# 06_-_CONNECTORS_1.net
KiCad netlist of a schematic drawn in Altium Designer
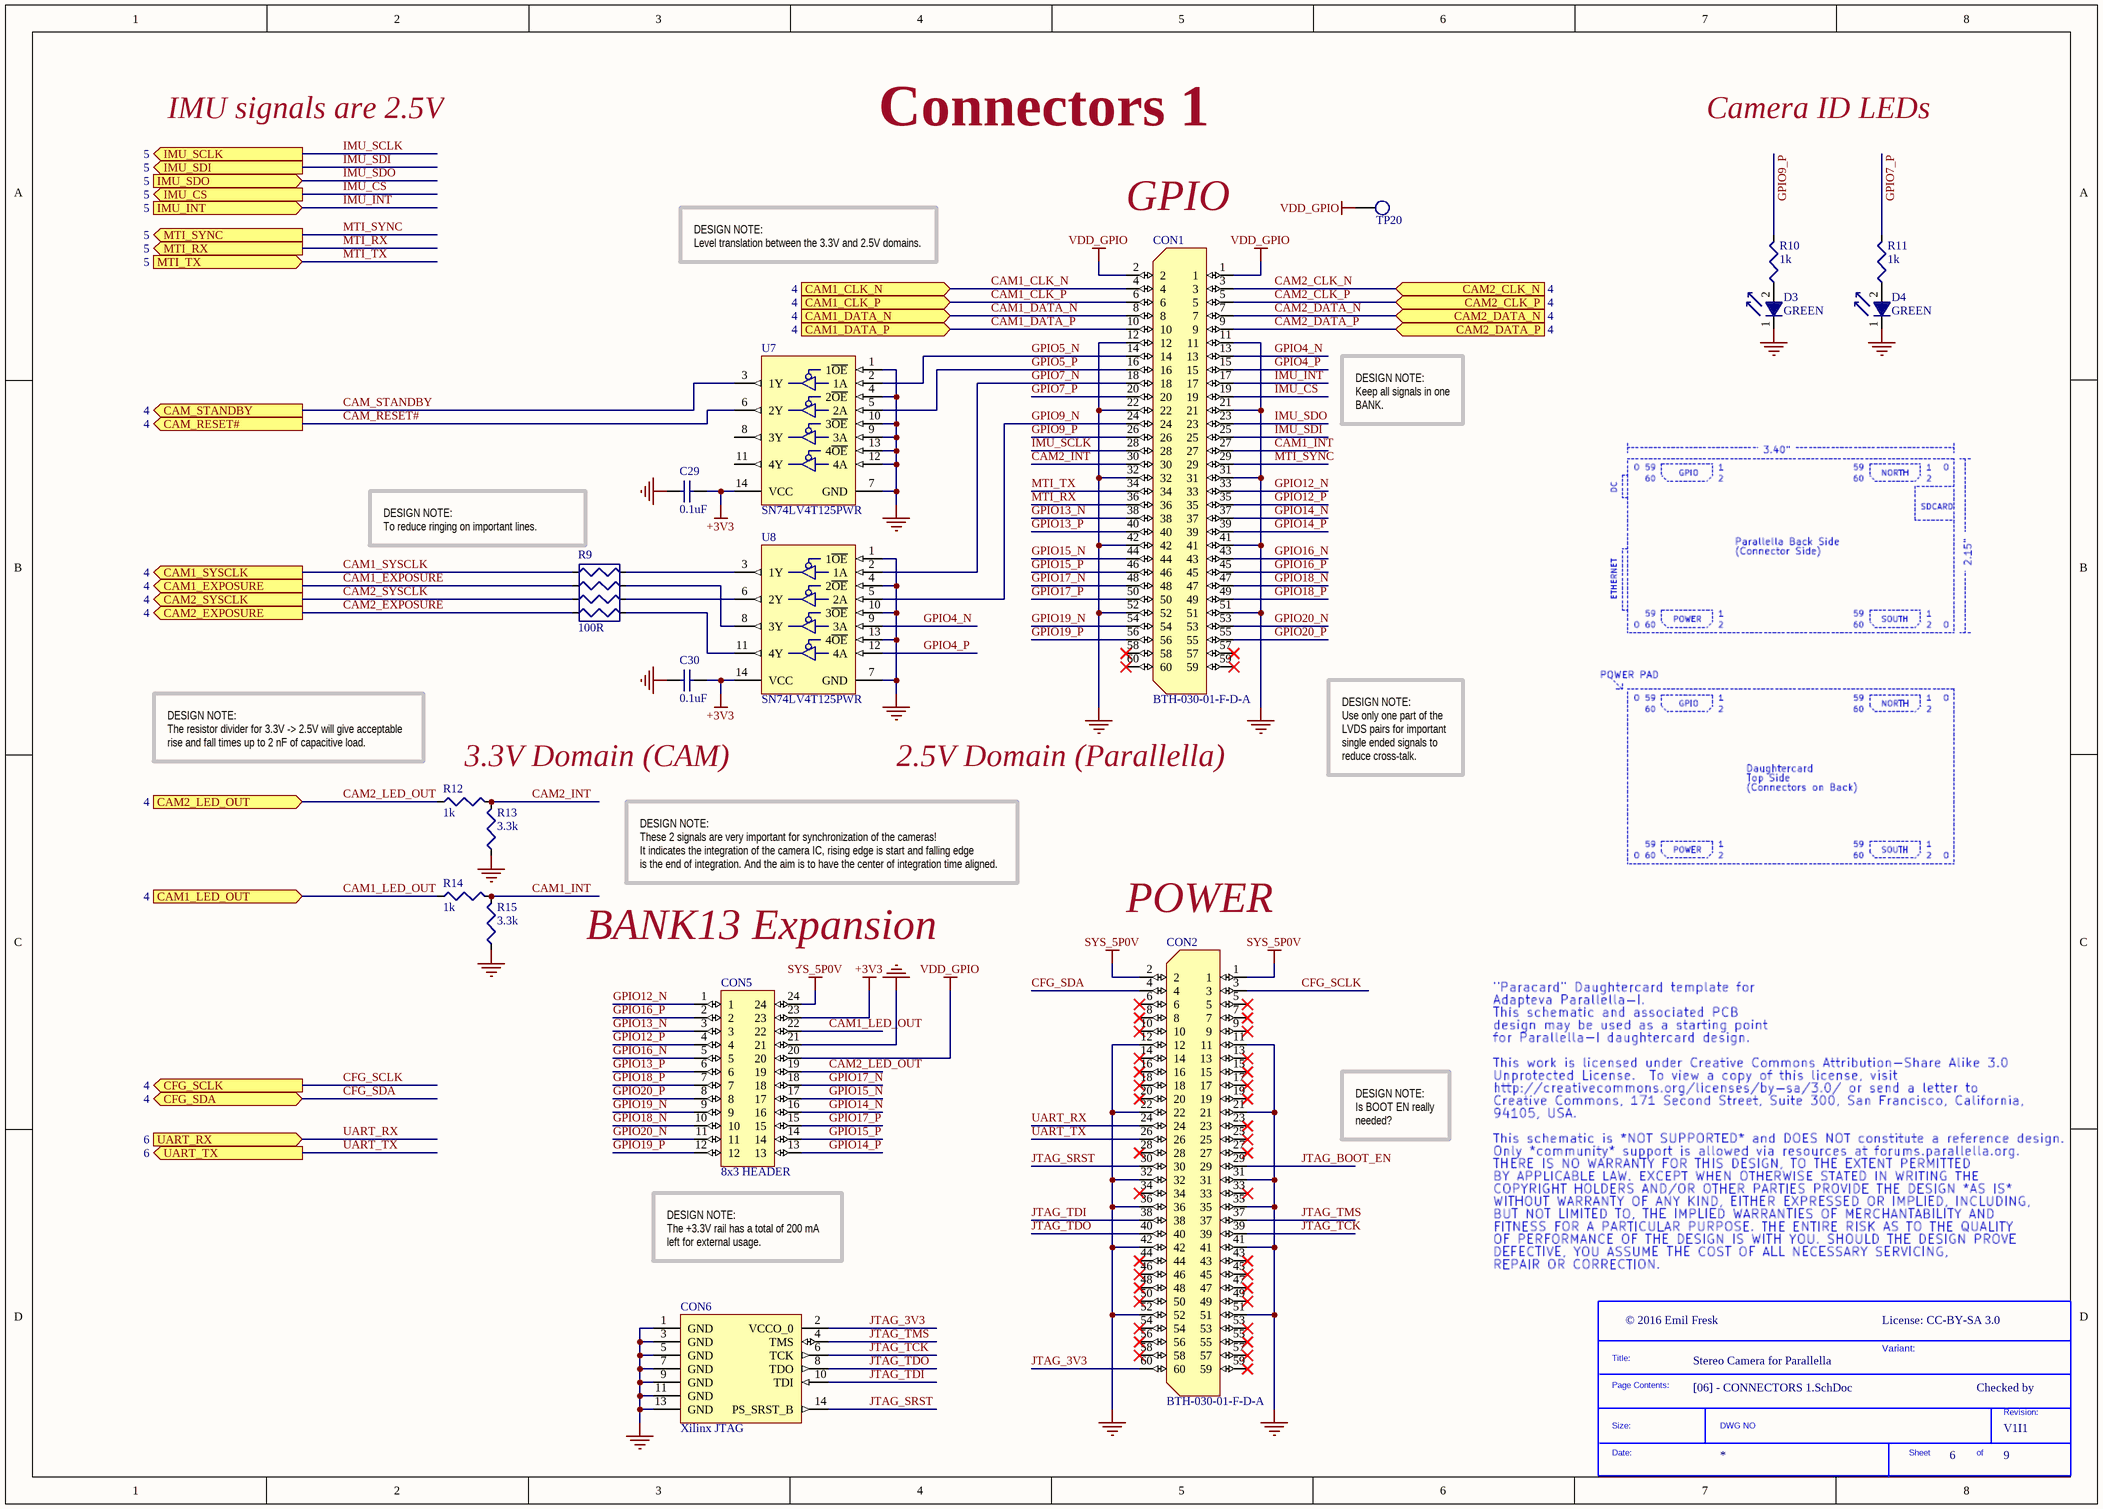
[diagram p0: [06] - CONNECTORS 1.SchDoc]

(export (version "E")
  (design (tool "Eeschema 10.0.6"))
  (components
    (comp (ref "C29")
      (value "0.1uF")
      (footprint "C0603L")
      (description "CAP CER 0.1UF 50V 10% X7R 0603")
      (fields
        (field (name "MANUFACTURER") "Murata Electronics North America")
        (field (name "MANUFACTURER PART NUMBER") "GRM188R71H104KA93J")
      )
      (libsource (lib "Capacitors") (part "GRM188R71H104KA93J"))
    )
    (comp (ref "C30")
      (value "0.1uF")
      (footprint "C0603L")
      (description "CAP CER 0.1UF 50V 10% X7R 0603")
      (fields
        (field (name "MANUFACTURER") "Murata Electronics North America")
        (field (name "MANUFACTURER PART NUMBER") "GRM188R71H104KA93J")
      )
      (libsource (lib "Capacitors") (part "GRM188R71H104KA93J"))
    )
    (comp (ref "CON1")
      (value "BTH-030-01-F-D-A")
      (footprint "BTH-030-01-X-D-A-K")
      (description "CONN RCPT 60POS 0.5MM SMD")
      (fields (field (name "MANUFACTURER") "Samtec Inc"))
      (libsource (lib "Connectors") (part "BTH-030-01-F-D-A"))
    )
    (comp (ref "CON2")
      (value "BTH-030-01-F-D-A")
      (footprint "BTH-030-01-X-D-A-K")
      (description "CONN RCPT 60POS 0.5MM SMD")
      (fields (field (name "MANUFACTURER") "Samtec Inc"))
      (libsource (lib "Connectors") (part "BTH-030-01-F-D-A"))
    )
    (comp (ref "CON5")
      (value "8x3 HEADER")
      (footprint "8x3HEADER_2.54mm")
      (libsource (lib "Connectors") (part "8x3 HEADER"))
    )
    (comp (ref "CON6")
      (value "Xilinx JTAG")
      (footprint "Xilinx JTAG Header")
      (libsource (lib "Connectors") (part "Xilinx JTAG"))
    )
    (comp (ref "D3")
      (value "GREEN")
      (footprint "LED0603_GREEN")
      (description "LED GREEN CLEAR 0603 SMD")
      (fields
        (field (name "MANUFACTURER") "Lite-On Inc")
        (field (name "MANUFACTURER PART NUMBER") "LTST-C190KGKT")
      )
      (libsource (lib "LEDs") (part "LTST-C190KGKT"))
    )
    (comp (ref "D4")
      (value "GREEN")
      (footprint "LED0603_GREEN")
      (description "LED GREEN CLEAR 0603 SMD")
      (fields
        (field (name "MANUFACTURER") "Lite-On Inc")
        (field (name "MANUFACTURER PART NUMBER") "LTST-C190KGKT")
      )
      (libsource (lib "LEDs") (part "LTST-C190KGKT"))
    )
    (comp (ref "R9")
      (value "100R")
      (footprint "CAC-80P319X159-8L")
      (description "RES ARRAY 100 OHM 4 RES 1206")
      (fields
        (field (name "MANUFACTURER") "Bourns Inc.")
        (field (name "MANUFACTURER PART NUMBER") "CAT16-101J4LF")
      )
      (libsource (lib "Resistors") (part "CAT16-101J4LF"))
    )
    (comp (ref "R10")
      (value "1k")
      (footprint "R0603L")
      (description "RES SMD 1K OHM 1% 1/10W 0603")
      (fields
        (field (name "MANUFACTURER") "Vishay Dale")
        (field (name "MANUFACTURER PART NUMBER") "CRCW06031K00FKEA")
      )
      (libsource (lib "Resistors") (part "CRCW06031K00FKEA"))
    )
    (comp (ref "R11")
      (value "1k")
      (footprint "R0603L")
      (description "RES SMD 1K OHM 1% 1/10W 0603")
      (fields
        (field (name "MANUFACTURER") "Vishay Dale")
        (field (name "MANUFACTURER PART NUMBER") "CRCW06031K00FKEA")
      )
      (libsource (lib "Resistors") (part "CRCW06031K00FKEA"))
    )
    (comp (ref "R12")
      (value "1k")
      (footprint "R0603L")
      (description "RES SMD 1K OHM 1% 1/10W 0603")
      (fields
        (field (name "MANUFACTURER") "Vishay Dale")
        (field (name "MANUFACTURER PART NUMBER") "CRCW06031K00FKEA")
      )
      (libsource (lib "Resistors") (part "CRCW06031K00FKEA"))
    )
    (comp (ref "R13")
      (value "3.3k")
      (footprint "R0603L")
      (description "RES 3.30K OHM 1/10W 1% 0603 SMD")
      (fields
        (field (name "MANUFACTURER") "Vishay Dale")
        (field (name "MANUFACTURER PART NUMBER") "CRCW06033K30FKEA")
      )
      (libsource (lib "Resistors") (part "CRCW06033K30FKEA"))
    )
    (comp (ref "R14")
      (value "1k")
      (footprint "R0603L")
      (description "RES SMD 1K OHM 1% 1/10W 0603")
      (fields
        (field (name "MANUFACTURER") "Vishay Dale")
        (field (name "MANUFACTURER PART NUMBER") "CRCW06031K00FKEA")
      )
      (libsource (lib "Resistors") (part "CRCW06031K00FKEA"))
    )
    (comp (ref "R15")
      (value "3.3k")
      (footprint "R0603L")
      (description "RES 3.30K OHM 1/10W 1% 0603 SMD")
      (fields
        (field (name "MANUFACTURER") "Vishay Dale")
        (field (name "MANUFACTURER PART NUMBER") "CRCW06033K30FKEA")
      )
      (libsource (lib "Resistors") (part "CRCW06033K30FKEA"))
    )
    (comp (ref "TP20")
      (value "TestPoint")
      (footprint "TestPoint_1.5mm")
      (libsource (lib "TestPoint") (part "TestPoint"))
    )
    (comp (ref "U7")
      (value "SN74LV4T125PWR")
      (footprint "TSSOP14N")
      (description "IC BUFF/DVR NON-INVERT 14TSSOP")
      (fields (field (name "MANUFACTURER") "Texas Instruments"))
      (libsource (lib "Level_Translators") (part "SN74LV4T125PWR"))
    )
    (comp (ref "U8")
      (value "SN74LV4T125PWR")
      (footprint "TSSOP14N")
      (description "IC BUFF/DVR NON-INVERT 14TSSOP")
      (fields (field (name "MANUFACTURER") "Texas Instruments"))
      (libsource (lib "Level_Translators") (part "SN74LV4T125PWR"))
    )
  )
  (nets
    (net (code "1") (name "+3V3") (class "Default")
      (node (ref "C29") (pin "2") (pinfunction "2_2") (pintype "passive"))
      (node (ref "C30") (pin "2") (pinfunction "2_2") (pintype "passive"))
      (node (ref "CON5") (pin "23") (pinfunction "23_23") (pintype "bidirectional"))
      (node (ref "U7") (pin "14") (pinfunction "VCC_14") (pintype "power_in"))
      (node (ref "U8") (pin "14") (pinfunction "VCC_14") (pintype "power_in"))
    )
    (net (code "2") (name "/CAM1_CLK_N") (class "Default")
      (node (ref "CON1") (pin "4") (pinfunction "4_4") (pintype "bidirectional"))
    )
    (net (code "3") (name "/CAM1_CLK_P") (class "Default")
      (node (ref "CON1") (pin "6") (pinfunction "6_6") (pintype "bidirectional"))
    )
    (net (code "4") (name "/CAM1_DATA_N") (class "Default")
      (node (ref "CON1") (pin "8") (pinfunction "8_8") (pintype "bidirectional"))
    )
    (net (code "5") (name "/CAM1_DATA_P") (class "Default")
      (node (ref "CON1") (pin "10") (pinfunction "10_10") (pintype "bidirectional"))
    )
    (net (code "6") (name "/CAM1_EXPOSURE") (class "Default")
      (node (ref "R9") (pin "2") (pinfunction "2_2") (pintype "passive"))
    )
    (net (code "7") (name "/CAM1_INT") (class "Default")
      (node (ref "CON1") (pin "27") (pinfunction "27_27") (pintype "bidirectional"))
      (node (ref "R14") (pin "2") (pinfunction "2_2") (pintype "passive"))
      (node (ref "R15") (pin "2") (pinfunction "2_2") (pintype "passive"))
    )
    (net (code "8") (name "/CAM1_LED_OUT") (class "Default")
      (node (ref "CON5") (pin "22") (pinfunction "22_22") (pintype "bidirectional"))
      (node (ref "R14") (pin "1") (pinfunction "1_1") (pintype "passive"))
    )
    (net (code "9") (name "/CAM1_SYSCLK") (class "Default")
      (node (ref "R9") (pin "1") (pinfunction "1_1") (pintype "passive"))
    )
    (net (code "10") (name "/CAM2_CLK_N") (class "Default")
      (node (ref "CON1") (pin "3") (pinfunction "3_3") (pintype "bidirectional"))
    )
    (net (code "11") (name "/CAM2_CLK_P") (class "Default")
      (node (ref "CON1") (pin "5") (pinfunction "5_5") (pintype "bidirectional"))
    )
    (net (code "12") (name "/CAM2_DATA_N") (class "Default")
      (node (ref "CON1") (pin "7") (pinfunction "7_7") (pintype "bidirectional"))
    )
    (net (code "13") (name "/CAM2_DATA_P") (class "Default")
      (node (ref "CON1") (pin "9") (pinfunction "9_9") (pintype "bidirectional"))
    )
    (net (code "14") (name "/CAM2_EXPOSURE") (class "Default")
      (node (ref "R9") (pin "4") (pinfunction "4_4") (pintype "passive"))
    )
    (net (code "15") (name "/CAM2_INT") (class "Default")
      (node (ref "CON1") (pin "30") (pinfunction "30_30") (pintype "bidirectional"))
      (node (ref "R12") (pin "2") (pinfunction "2_2") (pintype "passive"))
      (node (ref "R13") (pin "2") (pinfunction "2_2") (pintype "passive"))
    )
    (net (code "16") (name "/CAM2_LED_OUT") (class "Default")
      (node (ref "CON5") (pin "19") (pinfunction "19_19") (pintype "bidirectional"))
      (node (ref "R12") (pin "1") (pinfunction "1_1") (pintype "passive"))
    )
    (net (code "17") (name "/CAM2_SYSCLK") (class "Default")
      (node (ref "R9") (pin "3") (pinfunction "3_3") (pintype "passive"))
    )
    (net (code "18") (name "/CAM_RESET#") (class "Default")
      (node (ref "U7") (pin "6") (pinfunction "2Y_6") (pintype "output"))
    )
    (net (code "19") (name "/CAM_STANDBY") (class "Default")
      (node (ref "U7") (pin "3") (pinfunction "1Y_3") (pintype "output"))
    )
    (net (code "20") (name "/CFG_SCLK") (class "Default")
      (node (ref "CON2") (pin "3") (pinfunction "3_3") (pintype "bidirectional"))
    )
    (net (code "21") (name "/CFG_SDA") (class "Default")
      (node (ref "CON2") (pin "4") (pinfunction "4_4") (pintype "bidirectional"))
    )
    (net (code "22") (name "/GPIO4_N") (class "Default")
      (node (ref "CON1") (pin "13") (pinfunction "13_13") (pintype "bidirectional"))
      (node (ref "U8") (pin "9") (pinfunction "3A_9") (pintype "input"))
    )
    (net (code "23") (name "/GPIO4_P") (class "Default")
      (node (ref "CON1") (pin "15") (pinfunction "15_15") (pintype "bidirectional"))
      (node (ref "U8") (pin "12") (pinfunction "4A_12") (pintype "input"))
    )
    (net (code "24") (name "/GPIO5_N") (class "Default")
      (node (ref "CON1") (pin "14") (pinfunction "14_14") (pintype "bidirectional"))
      (node (ref "U7") (pin "2") (pinfunction "1A_2") (pintype "input"))
    )
    (net (code "25") (name "/GPIO5_P") (class "Default")
      (node (ref "CON1") (pin "16") (pinfunction "16_16") (pintype "bidirectional"))
      (node (ref "U7") (pin "5") (pinfunction "2A_5") (pintype "input"))
    )
    (net (code "26") (name "/GPIO7_N") (class "Default")
      (node (ref "CON1") (pin "18") (pinfunction "18_18") (pintype "bidirectional"))
      (node (ref "U8") (pin "2") (pinfunction "1A_2") (pintype "input"))
    )
    (net (code "27") (name "/GPIO7_P") (class "Default")
      (node (ref "CON1") (pin "20") (pinfunction "20_20") (pintype "bidirectional"))
      (node (ref "R11") (pin "2") (pinfunction "2_2") (pintype "passive"))
    )
    (net (code "28") (name "/GPIO9_N") (class "Default")
      (node (ref "CON1") (pin "24") (pinfunction "24_24") (pintype "bidirectional"))
      (node (ref "U8") (pin "5") (pinfunction "2A_5") (pintype "input"))
    )
    (net (code "29") (name "/GPIO9_P") (class "Default")
      (node (ref "CON1") (pin "26") (pinfunction "26_26") (pintype "bidirectional"))
      (node (ref "R10") (pin "2") (pinfunction "2_2") (pintype "passive"))
    )
    (net (code "30") (name "/GPIO12_N") (class "Default")
      (node (ref "CON1") (pin "33") (pinfunction "33_33") (pintype "bidirectional"))
      (node (ref "CON5") (pin "1") (pinfunction "1_1") (pintype "bidirectional"))
    )
    (net (code "31") (name "/GPIO12_P") (class "Default")
      (node (ref "CON1") (pin "35") (pinfunction "35_35") (pintype "bidirectional"))
      (node (ref "CON5") (pin "4") (pinfunction "4_4") (pintype "bidirectional"))
    )
    (net (code "32") (name "/GPIO13_N") (class "Default")
      (node (ref "CON1") (pin "38") (pinfunction "38_38") (pintype "bidirectional"))
      (node (ref "CON5") (pin "3") (pinfunction "3_3") (pintype "bidirectional"))
    )
    (net (code "33") (name "/GPIO13_P") (class "Default")
      (node (ref "CON1") (pin "40") (pinfunction "40_40") (pintype "bidirectional"))
      (node (ref "CON5") (pin "6") (pinfunction "6_6") (pintype "bidirectional"))
    )
    (net (code "34") (name "/GPIO14_N") (class "Default")
      (node (ref "CON1") (pin "37") (pinfunction "37_37") (pintype "bidirectional"))
      (node (ref "CON5") (pin "16") (pinfunction "16_16") (pintype "bidirectional"))
    )
    (net (code "35") (name "/GPIO14_P") (class "Default")
      (node (ref "CON1") (pin "39") (pinfunction "39_39") (pintype "bidirectional"))
      (node (ref "CON5") (pin "13") (pinfunction "13_13") (pintype "bidirectional"))
    )
    (net (code "36") (name "/GPIO15_N") (class "Default")
      (node (ref "CON1") (pin "44") (pinfunction "44_44") (pintype "bidirectional"))
      (node (ref "CON5") (pin "17") (pinfunction "17_17") (pintype "bidirectional"))
    )
    (net (code "37") (name "/GPIO15_P") (class "Default")
      (node (ref "CON1") (pin "46") (pinfunction "46_46") (pintype "bidirectional"))
      (node (ref "CON5") (pin "14") (pinfunction "14_14") (pintype "bidirectional"))
    )
    (net (code "38") (name "/GPIO16_N") (class "Default")
      (node (ref "CON1") (pin "43") (pinfunction "43_43") (pintype "bidirectional"))
      (node (ref "CON5") (pin "5") (pinfunction "5_5") (pintype "bidirectional"))
    )
    (net (code "39") (name "/GPIO16_P") (class "Default")
      (node (ref "CON1") (pin "45") (pinfunction "45_45") (pintype "bidirectional"))
      (node (ref "CON5") (pin "2") (pinfunction "2_2") (pintype "bidirectional"))
    )
    (net (code "40") (name "/GPIO17_N") (class "Default")
      (node (ref "CON1") (pin "48") (pinfunction "48_48") (pintype "bidirectional"))
      (node (ref "CON5") (pin "18") (pinfunction "18_18") (pintype "bidirectional"))
    )
    (net (code "41") (name "/GPIO17_P") (class "Default")
      (node (ref "CON1") (pin "50") (pinfunction "50_50") (pintype "bidirectional"))
      (node (ref "CON5") (pin "15") (pinfunction "15_15") (pintype "bidirectional"))
    )
    (net (code "42") (name "/GPIO18_N") (class "Default")
      (node (ref "CON1") (pin "47") (pinfunction "47_47") (pintype "bidirectional"))
      (node (ref "CON5") (pin "10") (pinfunction "10_10") (pintype "bidirectional"))
    )
    (net (code "43") (name "/GPIO18_P") (class "Default")
      (node (ref "CON1") (pin "49") (pinfunction "49_49") (pintype "bidirectional"))
      (node (ref "CON5") (pin "7") (pinfunction "7_7") (pintype "bidirectional"))
    )
    (net (code "44") (name "/GPIO19_N") (class "Default")
      (node (ref "CON1") (pin "54") (pinfunction "54_54") (pintype "bidirectional"))
      (node (ref "CON5") (pin "9") (pinfunction "9_9") (pintype "bidirectional"))
    )
    (net (code "45") (name "/GPIO19_P") (class "Default")
      (node (ref "CON1") (pin "56") (pinfunction "56_56") (pintype "bidirectional"))
      (node (ref "CON5") (pin "12") (pinfunction "12_12") (pintype "bidirectional"))
    )
    (net (code "46") (name "/GPIO20_N") (class "Default")
      (node (ref "CON1") (pin "53") (pinfunction "53_53") (pintype "bidirectional"))
      (node (ref "CON5") (pin "11") (pinfunction "11_11") (pintype "bidirectional"))
    )
    (net (code "47") (name "/GPIO20_P") (class "Default")
      (node (ref "CON1") (pin "55") (pinfunction "55_55") (pintype "bidirectional"))
      (node (ref "CON5") (pin "8") (pinfunction "8_8") (pintype "bidirectional"))
    )
    (net (code "48") (name "/IMU_CS") (class "Default")
      (node (ref "CON1") (pin "19") (pinfunction "19_19") (pintype "bidirectional"))
    )
    (net (code "49") (name "/IMU_INT") (class "Default")
      (node (ref "CON1") (pin "17") (pinfunction "17_17") (pintype "bidirectional"))
    )
    (net (code "50") (name "/IMU_SCLK") (class "Default")
      (node (ref "CON1") (pin "28") (pinfunction "28_28") (pintype "bidirectional"))
    )
    (net (code "51") (name "/IMU_SDI") (class "Default")
      (node (ref "CON1") (pin "25") (pinfunction "25_25") (pintype "bidirectional"))
    )
    (net (code "52") (name "/IMU_SDO") (class "Default")
      (node (ref "CON1") (pin "23") (pinfunction "23_23") (pintype "bidirectional"))
    )
    (net (code "53") (name "/JTAG_3V3") (class "Default")
      (node (ref "CON2") (pin "60") (pinfunction "60_60") (pintype "bidirectional"))
      (node (ref "CON6") (pin "2") (pinfunction "VCCO_0_2") (pintype "power_in"))
    )
    (net (code "54") (name "/JTAG_BOOT_EN") (class "Default")
      (node (ref "CON2") (pin "29") (pinfunction "29_29") (pintype "bidirectional"))
    )
    (net (code "55") (name "/JTAG_SRST") (class "Default")
      (node (ref "CON2") (pin "30") (pinfunction "30_30") (pintype "bidirectional"))
      (node (ref "CON6") (pin "14") (pinfunction "PS_SRST_B_14") (pintype "output"))
    )
    (net (code "56") (name "/JTAG_TCK") (class "Default")
      (node (ref "CON2") (pin "39") (pinfunction "39_39") (pintype "bidirectional"))
      (node (ref "CON6") (pin "6") (pinfunction "TCK_6") (pintype "output"))
    )
    (net (code "57") (name "/JTAG_TDI") (class "Default")
      (node (ref "CON2") (pin "38") (pinfunction "38_38") (pintype "bidirectional"))
      (node (ref "CON6") (pin "10") (pinfunction "TDI_10") (pintype "input"))
    )
    (net (code "58") (name "/JTAG_TDO") (class "Default")
      (node (ref "CON2") (pin "40") (pinfunction "40_40") (pintype "bidirectional"))
      (node (ref "CON6") (pin "8") (pinfunction "TDO_8") (pintype "output"))
    )
    (net (code "59") (name "/JTAG_TMS") (class "Default")
      (node (ref "CON2") (pin "37") (pinfunction "37_37") (pintype "bidirectional"))
      (node (ref "CON6") (pin "4") (pinfunction "TMS_4") (pintype "bidirectional"))
    )
    (net (code "60") (name "/MTI_RX") (class "Default")
      (node (ref "CON1") (pin "36") (pinfunction "36_36") (pintype "bidirectional"))
    )
    (net (code "61") (name "/MTI_SYNC") (class "Default")
      (node (ref "CON1") (pin "29") (pinfunction "29_29") (pintype "bidirectional"))
    )
    (net (code "62") (name "/MTI_TX") (class "Default")
      (node (ref "CON1") (pin "34") (pinfunction "34_34") (pintype "bidirectional"))
    )
    (net (code "63") (name "/UART_RX") (class "Default")
      (node (ref "CON2") (pin "24") (pinfunction "24_24") (pintype "bidirectional"))
    )
    (net (code "64") (name "/UART_TX") (class "Default")
      (node (ref "CON2") (pin "26") (pinfunction "26_26") (pintype "bidirectional"))
    )
    (net (code "65") (name "GND") (class "Default")
      (node (ref "C29") (pin "1") (pinfunction "1_1") (pintype "passive"))
      (node (ref "C30") (pin "1") (pinfunction "1_1") (pintype "passive"))
      (node (ref "CON1") (pin "11") (pinfunction "11_11") (pintype "bidirectional"))
      (node (ref "CON1") (pin "12") (pinfunction "12_12") (pintype "bidirectional"))
      (node (ref "CON1") (pin "21") (pinfunction "21_21") (pintype "bidirectional"))
      (node (ref "CON1") (pin "22") (pinfunction "22_22") (pintype "bidirectional"))
      (node (ref "CON1") (pin "31") (pinfunction "31_31") (pintype "bidirectional"))
      (node (ref "CON1") (pin "32") (pinfunction "32_32") (pintype "bidirectional"))
      (node (ref "CON1") (pin "41") (pinfunction "41_41") (pintype "bidirectional"))
      (node (ref "CON1") (pin "42") (pinfunction "42_42") (pintype "bidirectional"))
      (node (ref "CON1") (pin "51") (pinfunction "51_51") (pintype "bidirectional"))
      (node (ref "CON1") (pin "52") (pinfunction "52_52") (pintype "bidirectional"))
      (node (ref "CON2") (pin "11") (pinfunction "11_11") (pintype "bidirectional"))
      (node (ref "CON2") (pin "12") (pinfunction "12_12") (pintype "bidirectional"))
      (node (ref "CON2") (pin "21") (pinfunction "21_21") (pintype "bidirectional"))
      (node (ref "CON2") (pin "22") (pinfunction "22_22") (pintype "bidirectional"))
      (node (ref "CON2") (pin "31") (pinfunction "31_31") (pintype "bidirectional"))
      (node (ref "CON2") (pin "32") (pinfunction "32_32") (pintype "bidirectional"))
      (node (ref "CON2") (pin "35") (pinfunction "35_35") (pintype "bidirectional"))
      (node (ref "CON2") (pin "36") (pinfunction "36_36") (pintype "bidirectional"))
      (node (ref "CON2") (pin "41") (pinfunction "41_41") (pintype "bidirectional"))
      (node (ref "CON2") (pin "42") (pinfunction "42_42") (pintype "bidirectional"))
      (node (ref "CON2") (pin "51") (pinfunction "51_51") (pintype "bidirectional"))
      (node (ref "CON2") (pin "52") (pinfunction "52_52") (pintype "bidirectional"))
      (node (ref "CON5") (pin "21") (pinfunction "21_21") (pintype "bidirectional"))
      (node (ref "CON6") (pin "1") (pinfunction "GND_1") (pintype "power_in"))
      (node (ref "CON6") (pin "11") (pinfunction "GND_11") (pintype "power_in"))
      (node (ref "CON6") (pin "13") (pinfunction "GND_13") (pintype "power_in"))
      (node (ref "CON6") (pin "3") (pinfunction "GND_3") (pintype "power_in"))
      (node (ref "CON6") (pin "5") (pinfunction "GND_5") (pintype "power_in"))
      (node (ref "CON6") (pin "7") (pinfunction "GND_7") (pintype "power_in"))
      (node (ref "CON6") (pin "9") (pinfunction "GND_9") (pintype "power_in"))
      (node (ref "D3") (pin "1") (pinfunction "1_1") (pintype "passive"))
      (node (ref "D4") (pin "1") (pinfunction "1_1") (pintype "passive"))
      (node (ref "R13") (pin "1") (pinfunction "1_1") (pintype "passive"))
      (node (ref "R15") (pin "1") (pinfunction "1_1") (pintype "passive"))
      (node (ref "U7") (pin "1") (pinfunction "1~{OE}_1") (pintype "input"))
      (node (ref "U7") (pin "10") (pinfunction "3~{OE}_10") (pintype "input"))
      (node (ref "U7") (pin "12") (pinfunction "4A_12") (pintype "input"))
      (node (ref "U7") (pin "13") (pinfunction "4~{OE}_13") (pintype "input"))
      (node (ref "U7") (pin "4") (pinfunction "2~{OE}_4") (pintype "input"))
      (node (ref "U7") (pin "7") (pinfunction "GND_7") (pintype "power_in"))
      (node (ref "U7") (pin "9") (pinfunction "3A_9") (pintype "input"))
      (node (ref "U8") (pin "1") (pinfunction "1~{OE}_1") (pintype "input"))
      (node (ref "U8") (pin "10") (pinfunction "3~{OE}_10") (pintype "input"))
      (node (ref "U8") (pin "13") (pinfunction "4~{OE}_13") (pintype "input"))
      (node (ref "U8") (pin "4") (pinfunction "2~{OE}_4") (pintype "input"))
      (node (ref "U8") (pin "7") (pinfunction "GND_7") (pintype "power_in"))
    )
    (net (code "66") (name "Net-(D3-Pad2)") (class "Default")
      (node (ref "D3") (pin "2") (pinfunction "2_2") (pintype "passive"))
      (node (ref "R10") (pin "1") (pinfunction "1_1") (pintype "passive"))
    )
    (net (code "67") (name "Net-(D4-Pad2)") (class "Default")
      (node (ref "D4") (pin "2") (pinfunction "2_2") (pintype "passive"))
      (node (ref "R11") (pin "1") (pinfunction "1_1") (pintype "passive"))
    )
    (net (code "68") (name "Net-(U8-1Y)") (class "Default")
      (node (ref "R9") (pin "8") (pinfunction "8_8") (pintype "passive"))
      (node (ref "U8") (pin "3") (pinfunction "1Y_3") (pintype "output"))
    )
    (net (code "69") (name "Net-(U8-2Y)") (class "Default")
      (node (ref "R9") (pin "6") (pinfunction "6_6") (pintype "passive"))
      (node (ref "U8") (pin "6") (pinfunction "2Y_6") (pintype "output"))
    )
    (net (code "70") (name "Net-(U8-3Y)") (class "Default")
      (node (ref "R9") (pin "7") (pinfunction "7_7") (pintype "passive"))
      (node (ref "U8") (pin "8") (pinfunction "3Y_8") (pintype "output"))
    )
    (net (code "71") (name "Net-(U8-4Y)") (class "Default")
      (node (ref "R9") (pin "5") (pinfunction "5_5") (pintype "passive"))
      (node (ref "U8") (pin "11") (pinfunction "4Y_11") (pintype "output"))
    )
    (net (code "72") (name "SYS_5P0V") (class "Default")
      (node (ref "CON2") (pin "1") (pinfunction "1_1") (pintype "bidirectional"))
      (node (ref "CON2") (pin "2") (pinfunction "2_2") (pintype "bidirectional"))
      (node (ref "CON5") (pin "24") (pinfunction "24_24") (pintype "bidirectional"))
    )
    (net (code "73") (name "VDD_GPIO") (class "Default")
      (node (ref "CON1") (pin "1") (pinfunction "1_1") (pintype "bidirectional"))
      (node (ref "CON1") (pin "2") (pinfunction "2_2") (pintype "bidirectional"))
      (node (ref "CON5") (pin "20") (pinfunction "20_20") (pintype "bidirectional"))
      (node (ref "TP20") (pin "1") (pinfunction "1_1") (pintype "passive"))
    )
    (net (code "74") (name "unconnected-(CON1-Pad57)") (class "Default")
      (node (ref "CON1") (pin "57") (pinfunction "57_57") (pintype "bidirectional+no_connect"))
    )
    (net (code "75") (name "unconnected-(CON1-Pad58)") (class "Default")
      (node (ref "CON1") (pin "58") (pinfunction "58_58") (pintype "bidirectional+no_connect"))
    )
    (net (code "76") (name "unconnected-(CON1-Pad59)") (class "Default")
      (node (ref "CON1") (pin "59") (pinfunction "59_59") (pintype "bidirectional+no_connect"))
    )
    (net (code "77") (name "unconnected-(CON1-Pad60)") (class "Default")
      (node (ref "CON1") (pin "60") (pinfunction "60_60") (pintype "bidirectional+no_connect"))
    )
    (net (code "78") (name "unconnected-(CON2-Pad5)") (class "Default")
      (node (ref "CON2") (pin "5") (pinfunction "5_5") (pintype "bidirectional+no_connect"))
    )
    (net (code "79") (name "unconnected-(CON2-Pad6)") (class "Default")
      (node (ref "CON2") (pin "6") (pinfunction "6_6") (pintype "bidirectional+no_connect"))
    )
    (net (code "80") (name "unconnected-(CON2-Pad7)") (class "Default")
      (node (ref "CON2") (pin "7") (pinfunction "7_7") (pintype "bidirectional+no_connect"))
    )
    (net (code "81") (name "unconnected-(CON2-Pad8)") (class "Default")
      (node (ref "CON2") (pin "8") (pinfunction "8_8") (pintype "bidirectional+no_connect"))
    )
    (net (code "82") (name "unconnected-(CON2-Pad9)") (class "Default")
      (node (ref "CON2") (pin "9") (pinfunction "9_9") (pintype "bidirectional+no_connect"))
    )
    (net (code "83") (name "unconnected-(CON2-Pad10)") (class "Default")
      (node (ref "CON2") (pin "10") (pinfunction "10_10") (pintype "bidirectional+no_connect"))
    )
    (net (code "84") (name "unconnected-(CON2-Pad13)") (class "Default")
      (node (ref "CON2") (pin "13") (pinfunction "13_13") (pintype "bidirectional+no_connect"))
    )
    (net (code "85") (name "unconnected-(CON2-Pad14)") (class "Default")
      (node (ref "CON2") (pin "14") (pinfunction "14_14") (pintype "bidirectional+no_connect"))
    )
    (net (code "86") (name "unconnected-(CON2-Pad15)") (class "Default")
      (node (ref "CON2") (pin "15") (pinfunction "15_15") (pintype "bidirectional+no_connect"))
    )
    (net (code "87") (name "unconnected-(CON2-Pad16)") (class "Default")
      (node (ref "CON2") (pin "16") (pinfunction "16_16") (pintype "bidirectional+no_connect"))
    )
    (net (code "88") (name "unconnected-(CON2-Pad17)") (class "Default")
      (node (ref "CON2") (pin "17") (pinfunction "17_17") (pintype "bidirectional+no_connect"))
    )
    (net (code "89") (name "unconnected-(CON2-Pad18)") (class "Default")
      (node (ref "CON2") (pin "18") (pinfunction "18_18") (pintype "bidirectional+no_connect"))
    )
    (net (code "90") (name "unconnected-(CON2-Pad19)") (class "Default")
      (node (ref "CON2") (pin "19") (pinfunction "19_19") (pintype "bidirectional+no_connect"))
    )
    (net (code "91") (name "unconnected-(CON2-Pad20)") (class "Default")
      (node (ref "CON2") (pin "20") (pinfunction "20_20") (pintype "bidirectional+no_connect"))
    )
    (net (code "92") (name "unconnected-(CON2-Pad23)") (class "Default")
      (node (ref "CON2") (pin "23") (pinfunction "23_23") (pintype "bidirectional+no_connect"))
    )
    (net (code "93") (name "unconnected-(CON2-Pad25)") (class "Default")
      (node (ref "CON2") (pin "25") (pinfunction "25_25") (pintype "bidirectional+no_connect"))
    )
    (net (code "94") (name "unconnected-(CON2-Pad27)") (class "Default")
      (node (ref "CON2") (pin "27") (pinfunction "27_27") (pintype "bidirectional+no_connect"))
    )
    (net (code "95") (name "unconnected-(CON2-Pad28)") (class "Default")
      (node (ref "CON2") (pin "28") (pinfunction "28_28") (pintype "bidirectional+no_connect"))
    )
    (net (code "96") (name "unconnected-(CON2-Pad33)") (class "Default")
      (node (ref "CON2") (pin "33") (pinfunction "33_33") (pintype "bidirectional+no_connect"))
    )
    (net (code "97") (name "unconnected-(CON2-Pad34)") (class "Default")
      (node (ref "CON2") (pin "34") (pinfunction "34_34") (pintype "bidirectional+no_connect"))
    )
    (net (code "98") (name "unconnected-(CON2-Pad43)") (class "Default")
      (node (ref "CON2") (pin "43") (pinfunction "43_43") (pintype "bidirectional+no_connect"))
    )
    (net (code "99") (name "unconnected-(CON2-Pad44)") (class "Default")
      (node (ref "CON2") (pin "44") (pinfunction "44_44") (pintype "bidirectional+no_connect"))
    )
    (net (code "100") (name "unconnected-(CON2-Pad45)") (class "Default")
      (node (ref "CON2") (pin "45") (pinfunction "45_45") (pintype "bidirectional+no_connect"))
    )
    (net (code "101") (name "unconnected-(CON2-Pad46)") (class "Default")
      (node (ref "CON2") (pin "46") (pinfunction "46_46") (pintype "bidirectional+no_connect"))
    )
    (net (code "102") (name "unconnected-(CON2-Pad47)") (class "Default")
      (node (ref "CON2") (pin "47") (pinfunction "47_47") (pintype "bidirectional+no_connect"))
    )
    (net (code "103") (name "unconnected-(CON2-Pad48)") (class "Default")
      (node (ref "CON2") (pin "48") (pinfunction "48_48") (pintype "bidirectional+no_connect"))
    )
    (net (code "104") (name "unconnected-(CON2-Pad49)") (class "Default")
      (node (ref "CON2") (pin "49") (pinfunction "49_49") (pintype "bidirectional+no_connect"))
    )
    (net (code "105") (name "unconnected-(CON2-Pad50)") (class "Default")
      (node (ref "CON2") (pin "50") (pinfunction "50_50") (pintype "bidirectional+no_connect"))
    )
    (net (code "106") (name "unconnected-(CON2-Pad53)") (class "Default")
      (node (ref "CON2") (pin "53") (pinfunction "53_53") (pintype "bidirectional+no_connect"))
    )
    (net (code "107") (name "unconnected-(CON2-Pad54)") (class "Default")
      (node (ref "CON2") (pin "54") (pinfunction "54_54") (pintype "bidirectional+no_connect"))
    )
    (net (code "108") (name "unconnected-(CON2-Pad55)") (class "Default")
      (node (ref "CON2") (pin "55") (pinfunction "55_55") (pintype "bidirectional+no_connect"))
    )
    (net (code "109") (name "unconnected-(CON2-Pad56)") (class "Default")
      (node (ref "CON2") (pin "56") (pinfunction "56_56") (pintype "bidirectional+no_connect"))
    )
    (net (code "110") (name "unconnected-(CON2-Pad57)") (class "Default")
      (node (ref "CON2") (pin "57") (pinfunction "57_57") (pintype "bidirectional+no_connect"))
    )
    (net (code "111") (name "unconnected-(CON2-Pad58)") (class "Default")
      (node (ref "CON2") (pin "58") (pinfunction "58_58") (pintype "bidirectional+no_connect"))
    )
    (net (code "112") (name "unconnected-(CON2-Pad59)") (class "Default")
      (node (ref "CON2") (pin "59") (pinfunction "59_59") (pintype "bidirectional+no_connect"))
    )
    (net (code "113") (name "unconnected-(U7-3Y-Pad8)") (class "Default")
      (node (ref "U7") (pin "8") (pinfunction "3Y_8") (pintype "output"))
    )
    (net (code "114") (name "unconnected-(U7-4Y-Pad11)") (class "Default")
      (node (ref "U7") (pin "11") (pinfunction "4Y_11") (pintype "output"))
    )
  )
)
